# Teensy_Stromzaehler.net
KiCad netlist of a schematic drawn in EAGLE
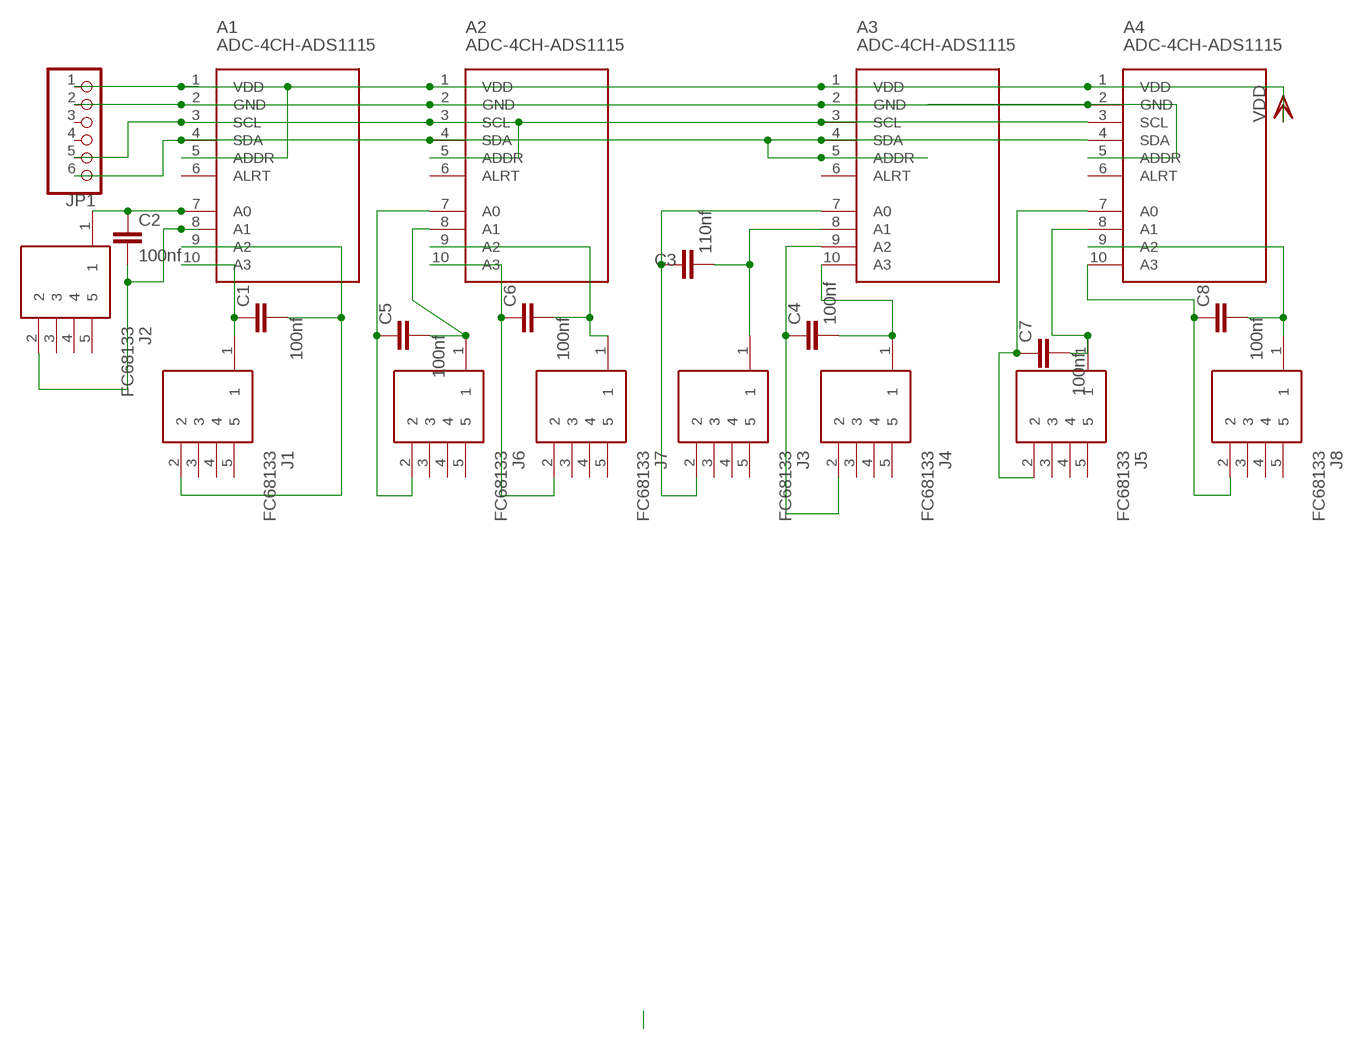
[diagram p0: schematic, sheet 1]

(export (version "E")
  (design (tool "Eeschema 10.0.6"))
  (components
    (comp (ref "A1")
      (value "ADC-4CH-ADS1115")
      (footprint "eagle-import:ADC-4CH-ADS1115")
      (libsource (lib "eagle-import") (part "ADC-4CH-ADS1115"))
    )
    (comp (ref "A2")
      (value "ADC-4CH-ADS1115")
      (footprint "eagle-import:ADC-4CH-ADS1115")
      (libsource (lib "eagle-import") (part "ADC-4CH-ADS1115"))
    )
    (comp (ref "A3")
      (value "ADC-4CH-ADS1115")
      (footprint "eagle-import:ADC-4CH-ADS1115")
      (libsource (lib "eagle-import") (part "ADC-4CH-ADS1115"))
    )
    (comp (ref "A4")
      (value "ADC-4CH-ADS1115")
      (footprint "eagle-import:ADC-4CH-ADS1115")
      (libsource (lib "eagle-import") (part "ADC-4CH-ADS1115"))
    )
    (comp (ref "C1")
      (value "100nf")
      (footprint "eagle-import:C025-024X044")
      (libsource (lib "eagle-import") (part "C-EU025-024X044"))
    )
    (comp (ref "C2")
      (value "100nf")
      (footprint "eagle-import:C025-024X044")
      (libsource (lib "eagle-import") (part "C-EU025-024X044"))
    )
    (comp (ref "C3")
      (value "110nf")
      (footprint "eagle-import:C025-024X044")
      (libsource (lib "eagle-import") (part "C-EU025-024X044"))
    )
    (comp (ref "C4")
      (value "100nf")
      (footprint "eagle-import:C025-024X044")
      (libsource (lib "eagle-import") (part "C-EU025-024X044"))
    )
    (comp (ref "C5")
      (value "100nf")
      (footprint "eagle-import:C025-024X044")
      (libsource (lib "eagle-import") (part "C-EU025-024X044"))
    )
    (comp (ref "C6")
      (value "100nf")
      (footprint "eagle-import:C025-024X044")
      (libsource (lib "eagle-import") (part "C-EU025-024X044"))
    )
    (comp (ref "C7")
      (value "100nf")
      (footprint "eagle-import:C025-024X044")
      (libsource (lib "eagle-import") (part "C-EU025-024X044"))
    )
    (comp (ref "C8")
      (value "100nf")
      (footprint "eagle-import:C025-024X044")
      (libsource (lib "eagle-import") (part "C-EU025-024X044"))
    )
    (comp (ref "J1")
      (value "FC68133")
      (footprint "eagle-import:FC68133")
      (libsource (lib "eagle-import") (part "FC68133"))
    )
    (comp (ref "J2")
      (value "FC68133")
      (footprint "eagle-import:FC68133")
      (libsource (lib "eagle-import") (part "FC68133"))
    )
    (comp (ref "J3")
      (value "FC68133")
      (footprint "eagle-import:FC68133")
      (libsource (lib "eagle-import") (part "FC68133"))
    )
    (comp (ref "J4")
      (value "FC68133")
      (footprint "eagle-import:FC68133")
      (libsource (lib "eagle-import") (part "FC68133"))
    )
    (comp (ref "J5")
      (value "FC68133")
      (footprint "eagle-import:FC68133")
      (libsource (lib "eagle-import") (part "FC68133"))
    )
    (comp (ref "J6")
      (value "FC68133")
      (footprint "eagle-import:FC68133")
      (libsource (lib "eagle-import") (part "FC68133"))
    )
    (comp (ref "J7")
      (value "FC68133")
      (footprint "eagle-import:FC68133")
      (libsource (lib "eagle-import") (part "FC68133"))
    )
    (comp (ref "J8")
      (value "FC68133")
      (footprint "eagle-import:FC68133")
      (libsource (lib "eagle-import") (part "FC68133"))
    )
    (comp (ref "JP1")
      (value "PINHD-1X6")
      (footprint "eagle-import:1X06")
      (libsource (lib "eagle-import") (part "PINHD-1X6"))
    )
  )
  (nets
    (net (code "1") (name "Net-(A1-A0)") (class "Default")
      (node (ref "A1") (pin "7") (pinfunction "A0_7") (pintype "input"))
      (node (ref "C2") (pin "1") (pinfunction "1_1") (pintype "passive"))
      (node (ref "J2") (pin "1") (pinfunction "1_1") (pintype "bidirectional"))
    )
    (net (code "2") (name "Net-(A1-A1)") (class "Default")
      (node (ref "A1") (pin "8") (pinfunction "A1_8") (pintype "input"))
      (node (ref "C2") (pin "2") (pinfunction "2_2") (pintype "passive"))
      (node (ref "J2") (pin "2") (pinfunction "2_2") (pintype "bidirectional"))
    )
    (net (code "3") (name "Net-(A1-A2)") (class "Default")
      (node (ref "A1") (pin "9") (pinfunction "A2_9") (pintype "input"))
      (node (ref "C1") (pin "2") (pinfunction "2_2") (pintype "passive"))
      (node (ref "J1") (pin "2") (pinfunction "2_2") (pintype "bidirectional"))
    )
    (net (code "4") (name "Net-(A1-A3)") (class "Default")
      (node (ref "A1") (pin "10") (pinfunction "A3_10") (pintype "input"))
      (node (ref "C1") (pin "1") (pinfunction "1_1") (pintype "passive"))
      (node (ref "J1") (pin "1") (pinfunction "1_1") (pintype "bidirectional"))
    )
    (net (code "5") (name "Net-(A1-GND)") (class "Default")
      (node (ref "A1") (pin "2") (pinfunction "GND_2") (pintype "power_in"))
      (node (ref "A2") (pin "2") (pinfunction "GND_2") (pintype "power_in"))
      (node (ref "A3") (pin "2") (pinfunction "GND_2") (pintype "power_in"))
      (node (ref "A4") (pin "2") (pinfunction "GND_2") (pintype "power_in"))
      (node (ref "A4") (pin "5") (pinfunction "ADDR_5") (pintype "bidirectional"))
      (node (ref "JP1") (pin "2") (pinfunction "2_2") (pintype "passive"))
    )
    (net (code "6") (name "Net-(A1-SCL)") (class "Default")
      (node (ref "A1") (pin "3") (pinfunction "SCL_3") (pintype "bidirectional"))
      (node (ref "A2") (pin "3") (pinfunction "SCL_3") (pintype "bidirectional"))
      (node (ref "A2") (pin "5") (pinfunction "ADDR_5") (pintype "bidirectional"))
      (node (ref "A3") (pin "3") (pinfunction "SCL_3") (pintype "bidirectional"))
      (node (ref "A4") (pin "3") (pinfunction "SCL_3") (pintype "bidirectional"))
      (node (ref "JP1") (pin "5") (pinfunction "5_5") (pintype "passive"))
    )
    (net (code "7") (name "Net-(A1-SDA)") (class "Default")
      (node (ref "A1") (pin "4") (pinfunction "SDA_4") (pintype "bidirectional"))
      (node (ref "A2") (pin "4") (pinfunction "SDA_4") (pintype "bidirectional"))
      (node (ref "A3") (pin "4") (pinfunction "SDA_4") (pintype "bidirectional"))
      (node (ref "A3") (pin "5") (pinfunction "ADDR_5") (pintype "bidirectional"))
      (node (ref "A4") (pin "4") (pinfunction "SDA_4") (pintype "bidirectional"))
      (node (ref "JP1") (pin "6") (pinfunction "6_6") (pintype "passive"))
    )
    (net (code "8") (name "Net-(A2-A0)") (class "Default")
      (node (ref "A2") (pin "7") (pinfunction "A0_7") (pintype "input"))
      (node (ref "C5") (pin "1") (pinfunction "1_1") (pintype "passive"))
      (node (ref "J6") (pin "2") (pinfunction "2_2") (pintype "bidirectional"))
    )
    (net (code "9") (name "Net-(A2-A1)") (class "Default")
      (node (ref "A2") (pin "8") (pinfunction "A1_8") (pintype "input"))
      (node (ref "C5") (pin "2") (pinfunction "2_2") (pintype "passive"))
      (node (ref "J6") (pin "1") (pinfunction "1_1") (pintype "bidirectional"))
    )
    (net (code "10") (name "Net-(A2-A2)") (class "Default")
      (node (ref "A2") (pin "9") (pinfunction "A2_9") (pintype "input"))
      (node (ref "C6") (pin "2") (pinfunction "2_2") (pintype "passive"))
      (node (ref "J7") (pin "1") (pinfunction "1_1") (pintype "bidirectional"))
    )
    (net (code "11") (name "Net-(A2-A3)") (class "Default")
      (node (ref "A2") (pin "10") (pinfunction "A3_10") (pintype "input"))
      (node (ref "C6") (pin "1") (pinfunction "1_1") (pintype "passive"))
      (node (ref "J7") (pin "2") (pinfunction "2_2") (pintype "bidirectional"))
    )
    (net (code "12") (name "Net-(A3-A0)") (class "Default")
      (node (ref "A3") (pin "7") (pinfunction "A0_7") (pintype "input"))
      (node (ref "C3") (pin "1") (pinfunction "1_1") (pintype "passive"))
      (node (ref "J3") (pin "2") (pinfunction "2_2") (pintype "bidirectional"))
    )
    (net (code "13") (name "Net-(A3-A1)") (class "Default")
      (node (ref "A3") (pin "8") (pinfunction "A1_8") (pintype "input"))
      (node (ref "C3") (pin "2") (pinfunction "2_2") (pintype "passive"))
      (node (ref "J3") (pin "1") (pinfunction "1_1") (pintype "bidirectional"))
    )
    (net (code "14") (name "Net-(A3-A2)") (class "Default")
      (node (ref "A3") (pin "9") (pinfunction "A2_9") (pintype "input"))
      (node (ref "C4") (pin "1") (pinfunction "1_1") (pintype "passive"))
      (node (ref "J4") (pin "2") (pinfunction "2_2") (pintype "bidirectional"))
    )
    (net (code "15") (name "Net-(A3-A3)") (class "Default")
      (node (ref "A3") (pin "10") (pinfunction "A3_10") (pintype "input"))
      (node (ref "C4") (pin "2") (pinfunction "2_2") (pintype "passive"))
      (node (ref "J4") (pin "1") (pinfunction "1_1") (pintype "bidirectional"))
    )
    (net (code "16") (name "Net-(A4-A0)") (class "Default")
      (node (ref "A4") (pin "7") (pinfunction "A0_7") (pintype "input"))
      (node (ref "C7") (pin "1") (pinfunction "1_1") (pintype "passive"))
      (node (ref "J5") (pin "2") (pinfunction "2_2") (pintype "bidirectional"))
    )
    (net (code "17") (name "Net-(A4-A1)") (class "Default")
      (node (ref "A4") (pin "8") (pinfunction "A1_8") (pintype "input"))
      (node (ref "C7") (pin "2") (pinfunction "2_2") (pintype "passive"))
      (node (ref "J5") (pin "1") (pinfunction "1_1") (pintype "bidirectional"))
    )
    (net (code "18") (name "Net-(A4-A2)") (class "Default")
      (node (ref "A4") (pin "9") (pinfunction "A2_9") (pintype "input"))
      (node (ref "C8") (pin "2") (pinfunction "2_2") (pintype "passive"))
      (node (ref "J8") (pin "1") (pinfunction "1_1") (pintype "bidirectional"))
    )
    (net (code "19") (name "Net-(A4-A3)") (class "Default")
      (node (ref "A4") (pin "10") (pinfunction "A3_10") (pintype "input"))
      (node (ref "C8") (pin "1") (pinfunction "1_1") (pintype "passive"))
      (node (ref "J8") (pin "2") (pinfunction "2_2") (pintype "bidirectional"))
    )
    (net (code "20") (name "VDD") (class "Default")
      (node (ref "A1") (pin "1") (pinfunction "VDD_1") (pintype "power_in"))
      (node (ref "A1") (pin "5") (pinfunction "ADDR_5") (pintype "bidirectional"))
      (node (ref "A2") (pin "1") (pinfunction "VDD_1") (pintype "power_in"))
      (node (ref "A3") (pin "1") (pinfunction "VDD_1") (pintype "power_in"))
      (node (ref "A4") (pin "1") (pinfunction "VDD_1") (pintype "power_in"))
      (node (ref "JP1") (pin "1") (pinfunction "1_1") (pintype "passive"))
    )
    (net (code "21") (name "unconnected-(A1-ALRT-Pad6)") (class "Default")
      (node (ref "A1") (pin "6") (pinfunction "ALRT_6") (pintype "bidirectional"))
    )
    (net (code "22") (name "unconnected-(A2-ALRT-Pad6)") (class "Default")
      (node (ref "A2") (pin "6") (pinfunction "ALRT_6") (pintype "bidirectional"))
    )
    (net (code "23") (name "unconnected-(A3-ALRT-Pad6)") (class "Default")
      (node (ref "A3") (pin "6") (pinfunction "ALRT_6") (pintype "bidirectional"))
    )
    (net (code "24") (name "unconnected-(A4-ALRT-Pad6)") (class "Default")
      (node (ref "A4") (pin "6") (pinfunction "ALRT_6") (pintype "bidirectional"))
    )
    (net (code "25") (name "unconnected-(J1-Pad3)") (class "Default")
      (node (ref "J1") (pin "3") (pinfunction "3_3") (pintype "bidirectional"))
    )
    (net (code "26") (name "unconnected-(J1-Pad4)") (class "Default")
      (node (ref "J1") (pin "4") (pinfunction "4_4") (pintype "bidirectional"))
    )
    (net (code "27") (name "unconnected-(J1-Pad5)") (class "Default")
      (node (ref "J1") (pin "5") (pinfunction "5_5") (pintype "bidirectional"))
    )
    (net (code "28") (name "unconnected-(J2-Pad3)") (class "Default")
      (node (ref "J2") (pin "3") (pinfunction "3_3") (pintype "bidirectional"))
    )
    (net (code "29") (name "unconnected-(J2-Pad4)") (class "Default")
      (node (ref "J2") (pin "4") (pinfunction "4_4") (pintype "bidirectional"))
    )
    (net (code "30") (name "unconnected-(J2-Pad5)") (class "Default")
      (node (ref "J2") (pin "5") (pinfunction "5_5") (pintype "bidirectional"))
    )
    (net (code "31") (name "unconnected-(J3-Pad3)") (class "Default")
      (node (ref "J3") (pin "3") (pinfunction "3_3") (pintype "bidirectional"))
    )
    (net (code "32") (name "unconnected-(J3-Pad4)") (class "Default")
      (node (ref "J3") (pin "4") (pinfunction "4_4") (pintype "bidirectional"))
    )
    (net (code "33") (name "unconnected-(J3-Pad5)") (class "Default")
      (node (ref "J3") (pin "5") (pinfunction "5_5") (pintype "bidirectional"))
    )
    (net (code "34") (name "unconnected-(J4-Pad3)") (class "Default")
      (node (ref "J4") (pin "3") (pinfunction "3_3") (pintype "bidirectional"))
    )
    (net (code "35") (name "unconnected-(J4-Pad4)") (class "Default")
      (node (ref "J4") (pin "4") (pinfunction "4_4") (pintype "bidirectional"))
    )
    (net (code "36") (name "unconnected-(J4-Pad5)") (class "Default")
      (node (ref "J4") (pin "5") (pinfunction "5_5") (pintype "bidirectional"))
    )
    (net (code "37") (name "unconnected-(J5-Pad3)") (class "Default")
      (node (ref "J5") (pin "3") (pinfunction "3_3") (pintype "bidirectional"))
    )
    (net (code "38") (name "unconnected-(J5-Pad4)") (class "Default")
      (node (ref "J5") (pin "4") (pinfunction "4_4") (pintype "bidirectional"))
    )
    (net (code "39") (name "unconnected-(J5-Pad5)") (class "Default")
      (node (ref "J5") (pin "5") (pinfunction "5_5") (pintype "bidirectional"))
    )
    (net (code "40") (name "unconnected-(J6-Pad3)") (class "Default")
      (node (ref "J6") (pin "3") (pinfunction "3_3") (pintype "bidirectional"))
    )
    (net (code "41") (name "unconnected-(J6-Pad4)") (class "Default")
      (node (ref "J6") (pin "4") (pinfunction "4_4") (pintype "bidirectional"))
    )
    (net (code "42") (name "unconnected-(J6-Pad5)") (class "Default")
      (node (ref "J6") (pin "5") (pinfunction "5_5") (pintype "bidirectional"))
    )
    (net (code "43") (name "unconnected-(J7-Pad3)") (class "Default")
      (node (ref "J7") (pin "3") (pinfunction "3_3") (pintype "bidirectional"))
    )
    (net (code "44") (name "unconnected-(J7-Pad4)") (class "Default")
      (node (ref "J7") (pin "4") (pinfunction "4_4") (pintype "bidirectional"))
    )
    (net (code "45") (name "unconnected-(J7-Pad5)") (class "Default")
      (node (ref "J7") (pin "5") (pinfunction "5_5") (pintype "bidirectional"))
    )
    (net (code "46") (name "unconnected-(J8-Pad3)") (class "Default")
      (node (ref "J8") (pin "3") (pinfunction "3_3") (pintype "bidirectional"))
    )
    (net (code "47") (name "unconnected-(J8-Pad4)") (class "Default")
      (node (ref "J8") (pin "4") (pinfunction "4_4") (pintype "bidirectional"))
    )
    (net (code "48") (name "unconnected-(J8-Pad5)") (class "Default")
      (node (ref "J8") (pin "5") (pinfunction "5_5") (pintype "bidirectional"))
    )
    (net (code "49") (name "unconnected-(JP1-Pad3)") (class "Default")
      (node (ref "JP1") (pin "3") (pinfunction "3_3") (pintype "passive"))
    )
    (net (code "50") (name "unconnected-(JP1-Pad4)") (class "Default")
      (node (ref "JP1") (pin "4") (pinfunction "4_4") (pintype "passive"))
    )
  )
)
